# adapter_v3.net
KiCad netlist of a schematic drawn in EAGLE
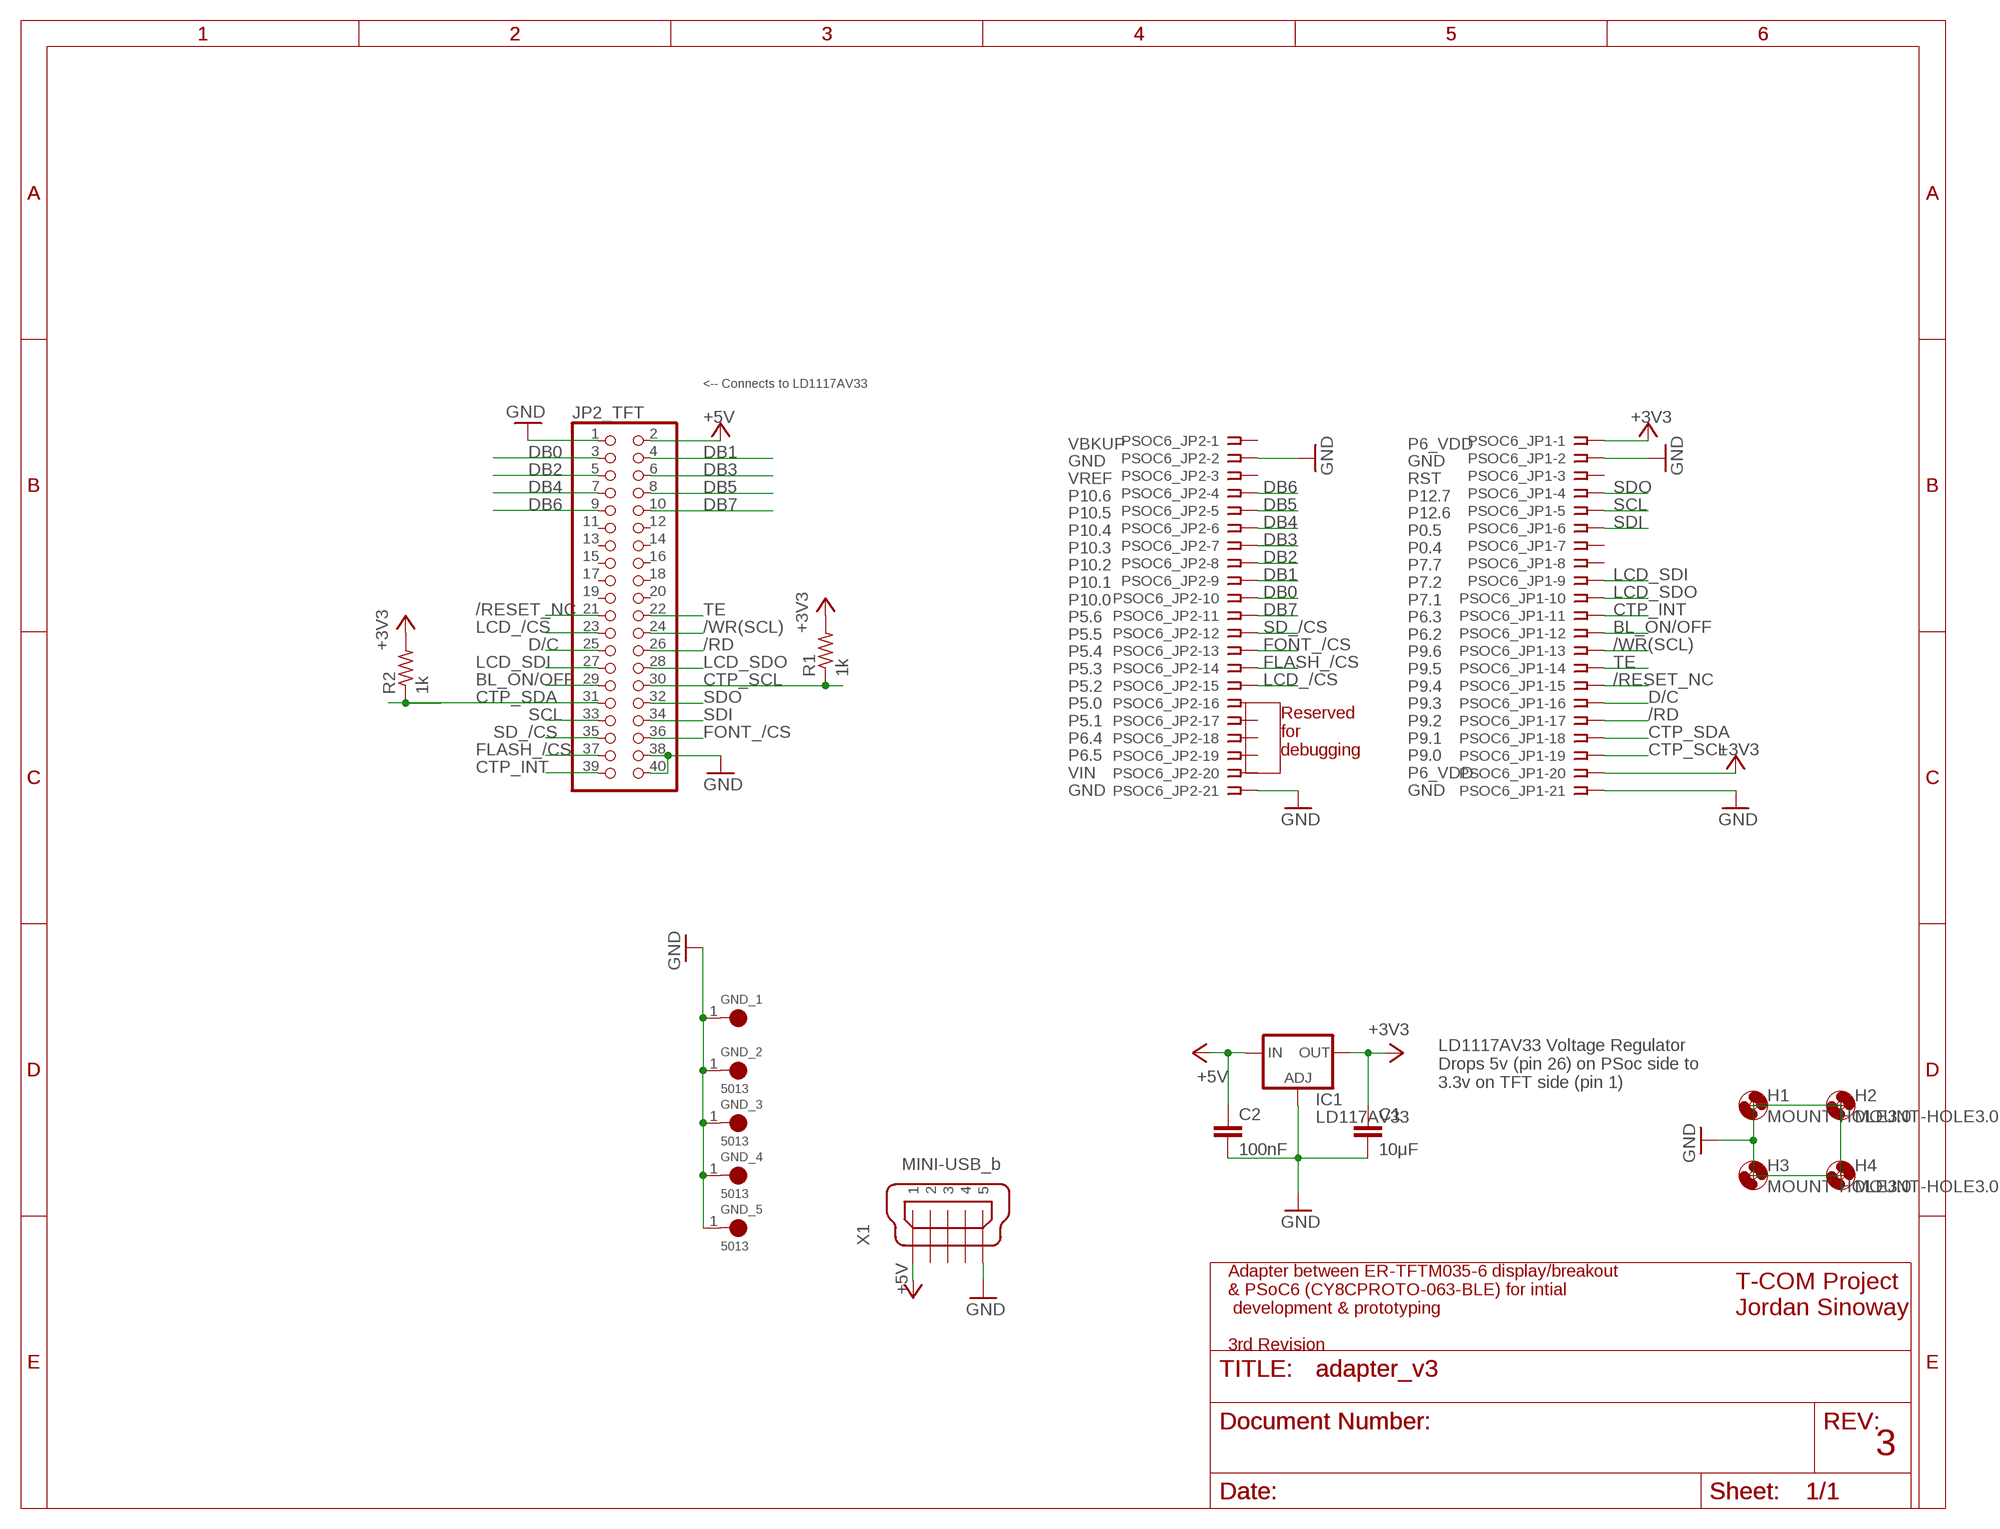
[diagram p0: schematic, sheet 1]

(export (version "E")
  (design (tool "Eeschema 10.0.6"))
  (components
    (comp (ref "C1")
      (value "10μF")
      (footprint "eagle-import:C2.5-2")
      (libsource (lib "eagle-import") (part "C2.5/2"))
    )
    (comp (ref "C2")
      (value "100nF")
      (footprint "eagle-import:C2.5-2")
      (libsource (lib "eagle-import") (part "C2.5/2"))
    )
    (comp (ref "GND_1")
      (value "5013")
      (footprint "eagle-import:TESTPOINT_5013")
      (fields (field (name "MF") "Keystone Electronics"))
      (libsource (lib "eagle-import") (part "5013"))
    )
    (comp (ref "GND_2")
      (value "5013")
      (footprint "eagle-import:TESTPOINT_5013")
      (fields (field (name "MF") "Keystone Electronics"))
      (libsource (lib "eagle-import") (part "5013"))
    )
    (comp (ref "GND_3")
      (value "5013")
      (footprint "eagle-import:TESTPOINT_5013")
      (fields (field (name "MF") "Keystone Electronics"))
      (libsource (lib "eagle-import") (part "5013"))
    )
    (comp (ref "GND_4")
      (value "5013")
      (footprint "eagle-import:TESTPOINT_5013")
      (fields (field (name "MF") "Keystone Electronics"))
      (libsource (lib "eagle-import") (part "5013"))
    )
    (comp (ref "GND_5")
      (value "5013")
      (footprint "eagle-import:TESTPOINT_5013")
      (fields (field (name "MF") "Keystone Electronics"))
      (libsource (lib "eagle-import") (part "5013"))
    )
    (comp (ref "H1")
      (value "MOUNT-HOLE3.0")
      (footprint "eagle-import:3,0")
      (libsource (lib "eagle-import") (part "MOUNT-HOLE3.0"))
    )
    (comp (ref "H2")
      (value "MOUNT-HOLE3.0")
      (footprint "eagle-import:3,0")
      (libsource (lib "eagle-import") (part "MOUNT-HOLE3.0"))
    )
    (comp (ref "H3")
      (value "MOUNT-HOLE3.0")
      (footprint "eagle-import:3,0")
      (libsource (lib "eagle-import") (part "MOUNT-HOLE3.0"))
    )
    (comp (ref "H4")
      (value "MOUNT-HOLE3.0")
      (footprint "eagle-import:3,0")
      (libsource (lib "eagle-import") (part "MOUNT-HOLE3.0"))
    )
    (comp (ref "IC1")
      (value "LD117AV33")
      (footprint "eagle-import:TO220L1")
      (libsource (lib "eagle-import") (part "LD117A?V33"))
    )
    (comp (ref "JP2_TFT")
      (value "PINHD-2X20")
      (footprint "eagle-import:2X20")
      (libsource (lib "eagle-import") (part "PINHD-2X20"))
    )
    (comp (ref "PSOC6_JP1")
      (value "SSW-121-02-G-S")
      (footprint "eagle-import:SSW-121-02-G-S")
      (fields (field (name "MF") "Samtec Inc."))
      (libsource (lib "eagle-import") (part "SSW-121-02-G-S"))
    )
    (comp (ref "PSOC6_JP2")
      (value "SSW-121-02-G-S")
      (footprint "eagle-import:SSW-121-02-G-S")
      (fields (field (name "MF") "Samtec Inc."))
      (libsource (lib "eagle-import") (part "SSW-121-02-G-S"))
    )
    (comp (ref "R1")
      (value "1k")
      (footprint "eagle-import:0204_7")
      (libsource (lib "eagle-import") (part "R-US_0204/7"))
    )
    (comp (ref "R2")
      (value "1k")
      (footprint "eagle-import:0204_7")
      (libsource (lib "eagle-import") (part "R-US_0204/7"))
    )
    (comp (ref "X1")
      (value "MINI-USB_b")
      (footprint "eagle-import:32005-601")
      (libsource (lib "eagle-import") (part "MINI-USB_SHIELD5P2-32005-601"))
    )
  )
  (nets
    (net (code "1") (name "+3V3") (class "Default")
      (node (ref "C1") (pin "1") (pinfunction "1_1") (pintype "passive"))
      (node (ref "IC1") (pin "2") (pinfunction "OUT_2") (pintype "passive"))
      (node (ref "PSOC6_JP1") (pin "1") (pinfunction "1_1") (pintype "passive"))
      (node (ref "PSOC6_JP1") (pin "20") (pinfunction "1_20") (pintype "passive"))
      (node (ref "R1") (pin "2") (pinfunction "2_2") (pintype "passive"))
      (node (ref "R2") (pin "2") (pinfunction "2_2") (pintype "passive"))
    )
    (net (code "2") (name "+5V") (class "Default")
      (node (ref "C2") (pin "1") (pinfunction "1_1") (pintype "passive"))
      (node (ref "IC1") (pin "3") (pinfunction "IN_3") (pintype "input"))
      (node (ref "JP2_TFT") (pin "2") (pinfunction "2_2") (pintype "passive"))
      (node (ref "X1") (pin "1") (pinfunction "1_1") (pintype "passive"))
    )
    (net (code "3") (name "/BL_ON{slash}OFF") (class "Default")
      (node (ref "JP2_TFT") (pin "29") (pinfunction "29_29") (pintype "passive"))
      (node (ref "PSOC6_JP1") (pin "12") (pinfunction "1_12") (pintype "passive"))
    )
    (net (code "4") (name "/CTP_INT") (class "Default")
      (node (ref "JP2_TFT") (pin "39") (pinfunction "39_39") (pintype "passive"))
      (node (ref "PSOC6_JP1") (pin "11") (pinfunction "1_11") (pintype "passive"))
    )
    (net (code "5") (name "/CTP_SCL") (class "Default")
      (node (ref "JP2_TFT") (pin "30") (pinfunction "30_30") (pintype "passive"))
      (node (ref "PSOC6_JP1") (pin "19") (pinfunction "1_19") (pintype "passive"))
      (node (ref "R1") (pin "1") (pinfunction "1_1") (pintype "passive"))
    )
    (net (code "6") (name "/CTP_SDA") (class "Default")
      (node (ref "JP2_TFT") (pin "31") (pinfunction "31_31") (pintype "passive"))
      (node (ref "PSOC6_JP1") (pin "18") (pinfunction "1_18") (pintype "passive"))
      (node (ref "R2") (pin "1") (pinfunction "1_1") (pintype "passive"))
    )
    (net (code "7") (name "/DB0") (class "Default")
      (node (ref "JP2_TFT") (pin "3") (pinfunction "3_3") (pintype "passive"))
      (node (ref "PSOC6_JP2") (pin "10") (pinfunction "1_10") (pintype "passive"))
    )
    (net (code "8") (name "/DB1") (class "Default")
      (node (ref "JP2_TFT") (pin "4") (pinfunction "4_4") (pintype "passive"))
      (node (ref "PSOC6_JP2") (pin "9") (pinfunction "1_9") (pintype "passive"))
    )
    (net (code "9") (name "/DB2") (class "Default")
      (node (ref "JP2_TFT") (pin "5") (pinfunction "5_5") (pintype "passive"))
      (node (ref "PSOC6_JP2") (pin "8") (pinfunction "1_8") (pintype "passive"))
    )
    (net (code "10") (name "/DB3") (class "Default")
      (node (ref "JP2_TFT") (pin "6") (pinfunction "6_6") (pintype "passive"))
      (node (ref "PSOC6_JP2") (pin "7") (pinfunction "1_7") (pintype "passive"))
    )
    (net (code "11") (name "/DB4") (class "Default")
      (node (ref "JP2_TFT") (pin "7") (pinfunction "7_7") (pintype "passive"))
      (node (ref "PSOC6_JP2") (pin "6") (pinfunction "1_6") (pintype "passive"))
    )
    (net (code "12") (name "/DB5") (class "Default")
      (node (ref "JP2_TFT") (pin "8") (pinfunction "8_8") (pintype "passive"))
      (node (ref "PSOC6_JP2") (pin "5") (pinfunction "1_5") (pintype "passive"))
    )
    (net (code "13") (name "/DB6") (class "Default")
      (node (ref "JP2_TFT") (pin "9") (pinfunction "9_9") (pintype "passive"))
      (node (ref "PSOC6_JP2") (pin "4") (pinfunction "1_4") (pintype "passive"))
    )
    (net (code "14") (name "/DB7") (class "Default")
      (node (ref "JP2_TFT") (pin "10") (pinfunction "10_10") (pintype "passive"))
      (node (ref "PSOC6_JP2") (pin "11") (pinfunction "1_11") (pintype "passive"))
    )
    (net (code "15") (name "/D{slash}C") (class "Default")
      (node (ref "JP2_TFT") (pin "25") (pinfunction "25_25") (pintype "passive"))
      (node (ref "PSOC6_JP1") (pin "16") (pinfunction "1_16") (pintype "passive"))
    )
    (net (code "16") (name "/FLASH_{slash}CS") (class "Default")
      (node (ref "JP2_TFT") (pin "37") (pinfunction "37_37") (pintype "passive"))
      (node (ref "PSOC6_JP2") (pin "14") (pinfunction "1_14") (pintype "passive"))
    )
    (net (code "17") (name "/FONT_{slash}CS") (class "Default")
      (node (ref "JP2_TFT") (pin "36") (pinfunction "36_36") (pintype "passive"))
      (node (ref "PSOC6_JP2") (pin "13") (pinfunction "1_13") (pintype "passive"))
    )
    (net (code "18") (name "/LCD_SDI") (class "Default")
      (node (ref "JP2_TFT") (pin "27") (pinfunction "27_27") (pintype "passive"))
      (node (ref "PSOC6_JP1") (pin "9") (pinfunction "1_9") (pintype "passive"))
    )
    (net (code "19") (name "/LCD_SDO") (class "Default")
      (node (ref "JP2_TFT") (pin "28") (pinfunction "28_28") (pintype "passive"))
      (node (ref "PSOC6_JP1") (pin "10") (pinfunction "1_10") (pintype "passive"))
    )
    (net (code "20") (name "/LCD_{slash}CS") (class "Default")
      (node (ref "JP2_TFT") (pin "23") (pinfunction "23_23") (pintype "passive"))
      (node (ref "PSOC6_JP2") (pin "15") (pinfunction "1_15") (pintype "passive"))
    )
    (net (code "21") (name "/SCL") (class "Default")
      (node (ref "JP2_TFT") (pin "33") (pinfunction "33_33") (pintype "passive"))
      (node (ref "PSOC6_JP1") (pin "5") (pinfunction "1_5") (pintype "passive"))
    )
    (net (code "22") (name "/SDI") (class "Default")
      (node (ref "JP2_TFT") (pin "34") (pinfunction "34_34") (pintype "passive"))
      (node (ref "PSOC6_JP1") (pin "6") (pinfunction "1_6") (pintype "passive"))
    )
    (net (code "23") (name "/SDO") (class "Default")
      (node (ref "JP2_TFT") (pin "32") (pinfunction "32_32") (pintype "passive"))
      (node (ref "PSOC6_JP1") (pin "4") (pinfunction "1_4") (pintype "passive"))
    )
    (net (code "24") (name "/SD_{slash}CS") (class "Default")
      (node (ref "JP2_TFT") (pin "35") (pinfunction "35_35") (pintype "passive"))
      (node (ref "PSOC6_JP2") (pin "12") (pinfunction "1_12") (pintype "passive"))
    )
    (net (code "25") (name "/TE") (class "Default")
      (node (ref "JP2_TFT") (pin "22") (pinfunction "22_22") (pintype "passive"))
      (node (ref "PSOC6_JP1") (pin "14") (pinfunction "1_14") (pintype "passive"))
    )
    (net (code "26") (name "/{slash}RD") (class "Default")
      (node (ref "JP2_TFT") (pin "26") (pinfunction "26_26") (pintype "passive"))
      (node (ref "PSOC6_JP1") (pin "17") (pinfunction "1_17") (pintype "passive"))
    )
    (net (code "27") (name "/{slash}RESET_NC") (class "Default")
      (node (ref "JP2_TFT") (pin "21") (pinfunction "21_21") (pintype "passive"))
      (node (ref "PSOC6_JP1") (pin "15") (pinfunction "1_15") (pintype "passive"))
    )
    (net (code "28") (name "/{slash}WR(SCL)") (class "Default")
      (node (ref "JP2_TFT") (pin "24") (pinfunction "24_24") (pintype "passive"))
      (node (ref "PSOC6_JP1") (pin "13") (pinfunction "1_13") (pintype "passive"))
    )
    (net (code "29") (name "GND") (class "Default")
      (node (ref "C1") (pin "2") (pinfunction "2_2") (pintype "passive"))
      (node (ref "C2") (pin "2") (pinfunction "2_2") (pintype "passive"))
      (node (ref "GND_1") (pin "1") (pinfunction "TP_1") (pintype "passive"))
      (node (ref "GND_2") (pin "1") (pinfunction "TP_1") (pintype "passive"))
      (node (ref "GND_3") (pin "1") (pinfunction "TP_1") (pintype "passive"))
      (node (ref "GND_4") (pin "1") (pinfunction "TP_1") (pintype "passive"))
      (node (ref "GND_5") (pin "1") (pinfunction "TP_1") (pintype "passive"))
      (node (ref "IC1") (pin "1") (pinfunction "ADJ_1") (pintype "input"))
      (node (ref "JP2_TFT") (pin "1") (pinfunction "1_1") (pintype "passive"))
      (node (ref "JP2_TFT") (pin "38") (pinfunction "38_38") (pintype "passive"))
      (node (ref "JP2_TFT") (pin "40") (pinfunction "40_40") (pintype "passive"))
      (node (ref "PSOC6_JP1") (pin "2") (pinfunction "1_2") (pintype "passive"))
      (node (ref "PSOC6_JP1") (pin "21") (pinfunction "1_21") (pintype "passive"))
      (node (ref "PSOC6_JP2") (pin "2") (pinfunction "1_2") (pintype "passive"))
      (node (ref "PSOC6_JP2") (pin "21") (pinfunction "1_21") (pintype "passive"))
      (node (ref "X1") (pin "5") (pinfunction "5_5") (pintype "passive"))
    )
    (net (code "30") (name "unconnected-(JP2_TFT-Pad11)") (class "Default")
      (node (ref "JP2_TFT") (pin "11") (pinfunction "11_11") (pintype "passive"))
    )
    (net (code "31") (name "unconnected-(JP2_TFT-Pad12)") (class "Default")
      (node (ref "JP2_TFT") (pin "12") (pinfunction "12_12") (pintype "passive"))
    )
    (net (code "32") (name "unconnected-(JP2_TFT-Pad13)") (class "Default")
      (node (ref "JP2_TFT") (pin "13") (pinfunction "13_13") (pintype "passive"))
    )
    (net (code "33") (name "unconnected-(JP2_TFT-Pad14)") (class "Default")
      (node (ref "JP2_TFT") (pin "14") (pinfunction "14_14") (pintype "passive"))
    )
    (net (code "34") (name "unconnected-(JP2_TFT-Pad15)") (class "Default")
      (node (ref "JP2_TFT") (pin "15") (pinfunction "15_15") (pintype "passive"))
    )
    (net (code "35") (name "unconnected-(JP2_TFT-Pad16)") (class "Default")
      (node (ref "JP2_TFT") (pin "16") (pinfunction "16_16") (pintype "passive"))
    )
    (net (code "36") (name "unconnected-(JP2_TFT-Pad17)") (class "Default")
      (node (ref "JP2_TFT") (pin "17") (pinfunction "17_17") (pintype "passive"))
    )
    (net (code "37") (name "unconnected-(JP2_TFT-Pad18)") (class "Default")
      (node (ref "JP2_TFT") (pin "18") (pinfunction "18_18") (pintype "passive"))
    )
    (net (code "38") (name "unconnected-(JP2_TFT-Pad19)") (class "Default")
      (node (ref "JP2_TFT") (pin "19") (pinfunction "19_19") (pintype "passive"))
    )
    (net (code "39") (name "unconnected-(JP2_TFT-Pad20)") (class "Default")
      (node (ref "JP2_TFT") (pin "20") (pinfunction "20_20") (pintype "passive"))
    )
    (net (code "40") (name "unconnected-(PSOC6_JP1O-1-Pad3)") (class "Default")
      (node (ref "PSOC6_JP1") (pin "3") (pinfunction "1_3") (pintype "passive"))
    )
    (net (code "41") (name "unconnected-(PSOC6_JP1S-1-Pad7)") (class "Default")
      (node (ref "PSOC6_JP1") (pin "7") (pinfunction "1_7") (pintype "passive"))
    )
    (net (code "42") (name "unconnected-(PSOC6_JP1T-1-Pad8)") (class "Default")
      (node (ref "PSOC6_JP1") (pin "8") (pinfunction "1_8") (pintype "passive"))
    )
    (net (code "43") (name "unconnected-(PSOC6_JP2-Pad1)") (class "Default")
      (node (ref "PSOC6_JP2") (pin "1") (pinfunction "1_1") (pintype "passive"))
    )
    (net (code "44") (name "unconnected-(PSOC6_JP2H-1-Pad16)") (class "Default")
      (node (ref "PSOC6_JP2") (pin "16") (pinfunction "1_16") (pintype "passive"))
    )
    (net (code "45") (name "unconnected-(PSOC6_JP2I-1-Pad17)") (class "Default")
      (node (ref "PSOC6_JP2") (pin "17") (pinfunction "1_17") (pintype "passive"))
    )
    (net (code "46") (name "unconnected-(PSOC6_JP2J-1-Pad18)") (class "Default")
      (node (ref "PSOC6_JP2") (pin "18") (pinfunction "1_18") (pintype "passive"))
    )
    (net (code "47") (name "unconnected-(PSOC6_JP2K-1-Pad19)") (class "Default")
      (node (ref "PSOC6_JP2") (pin "19") (pinfunction "1_19") (pintype "passive"))
    )
    (net (code "48") (name "unconnected-(PSOC6_JP2M-1-Pad20)") (class "Default")
      (node (ref "PSOC6_JP2") (pin "20") (pinfunction "1_20") (pintype "passive"))
    )
    (net (code "49") (name "unconnected-(PSOC6_JP2O-1-Pad3)") (class "Default")
      (node (ref "PSOC6_JP2") (pin "3") (pinfunction "1_3") (pintype "passive"))
    )
    (net (code "50") (name "unconnected-(X1-Pad2)") (class "Default")
      (node (ref "X1") (pin "2") (pinfunction "2_2") (pintype "passive"))
    )
    (net (code "51") (name "unconnected-(X1-Pad3)") (class "Default")
      (node (ref "X1") (pin "3") (pinfunction "3_3") (pintype "passive"))
    )
    (net (code "52") (name "unconnected-(X1-Pad4)") (class "Default")
      (node (ref "X1") (pin "4") (pinfunction "4_4") (pintype "passive"))
    )
  )
)
